# 04_LMS7002M_Misc.net
KiCad netlist of a schematic drawn in Altium Designer
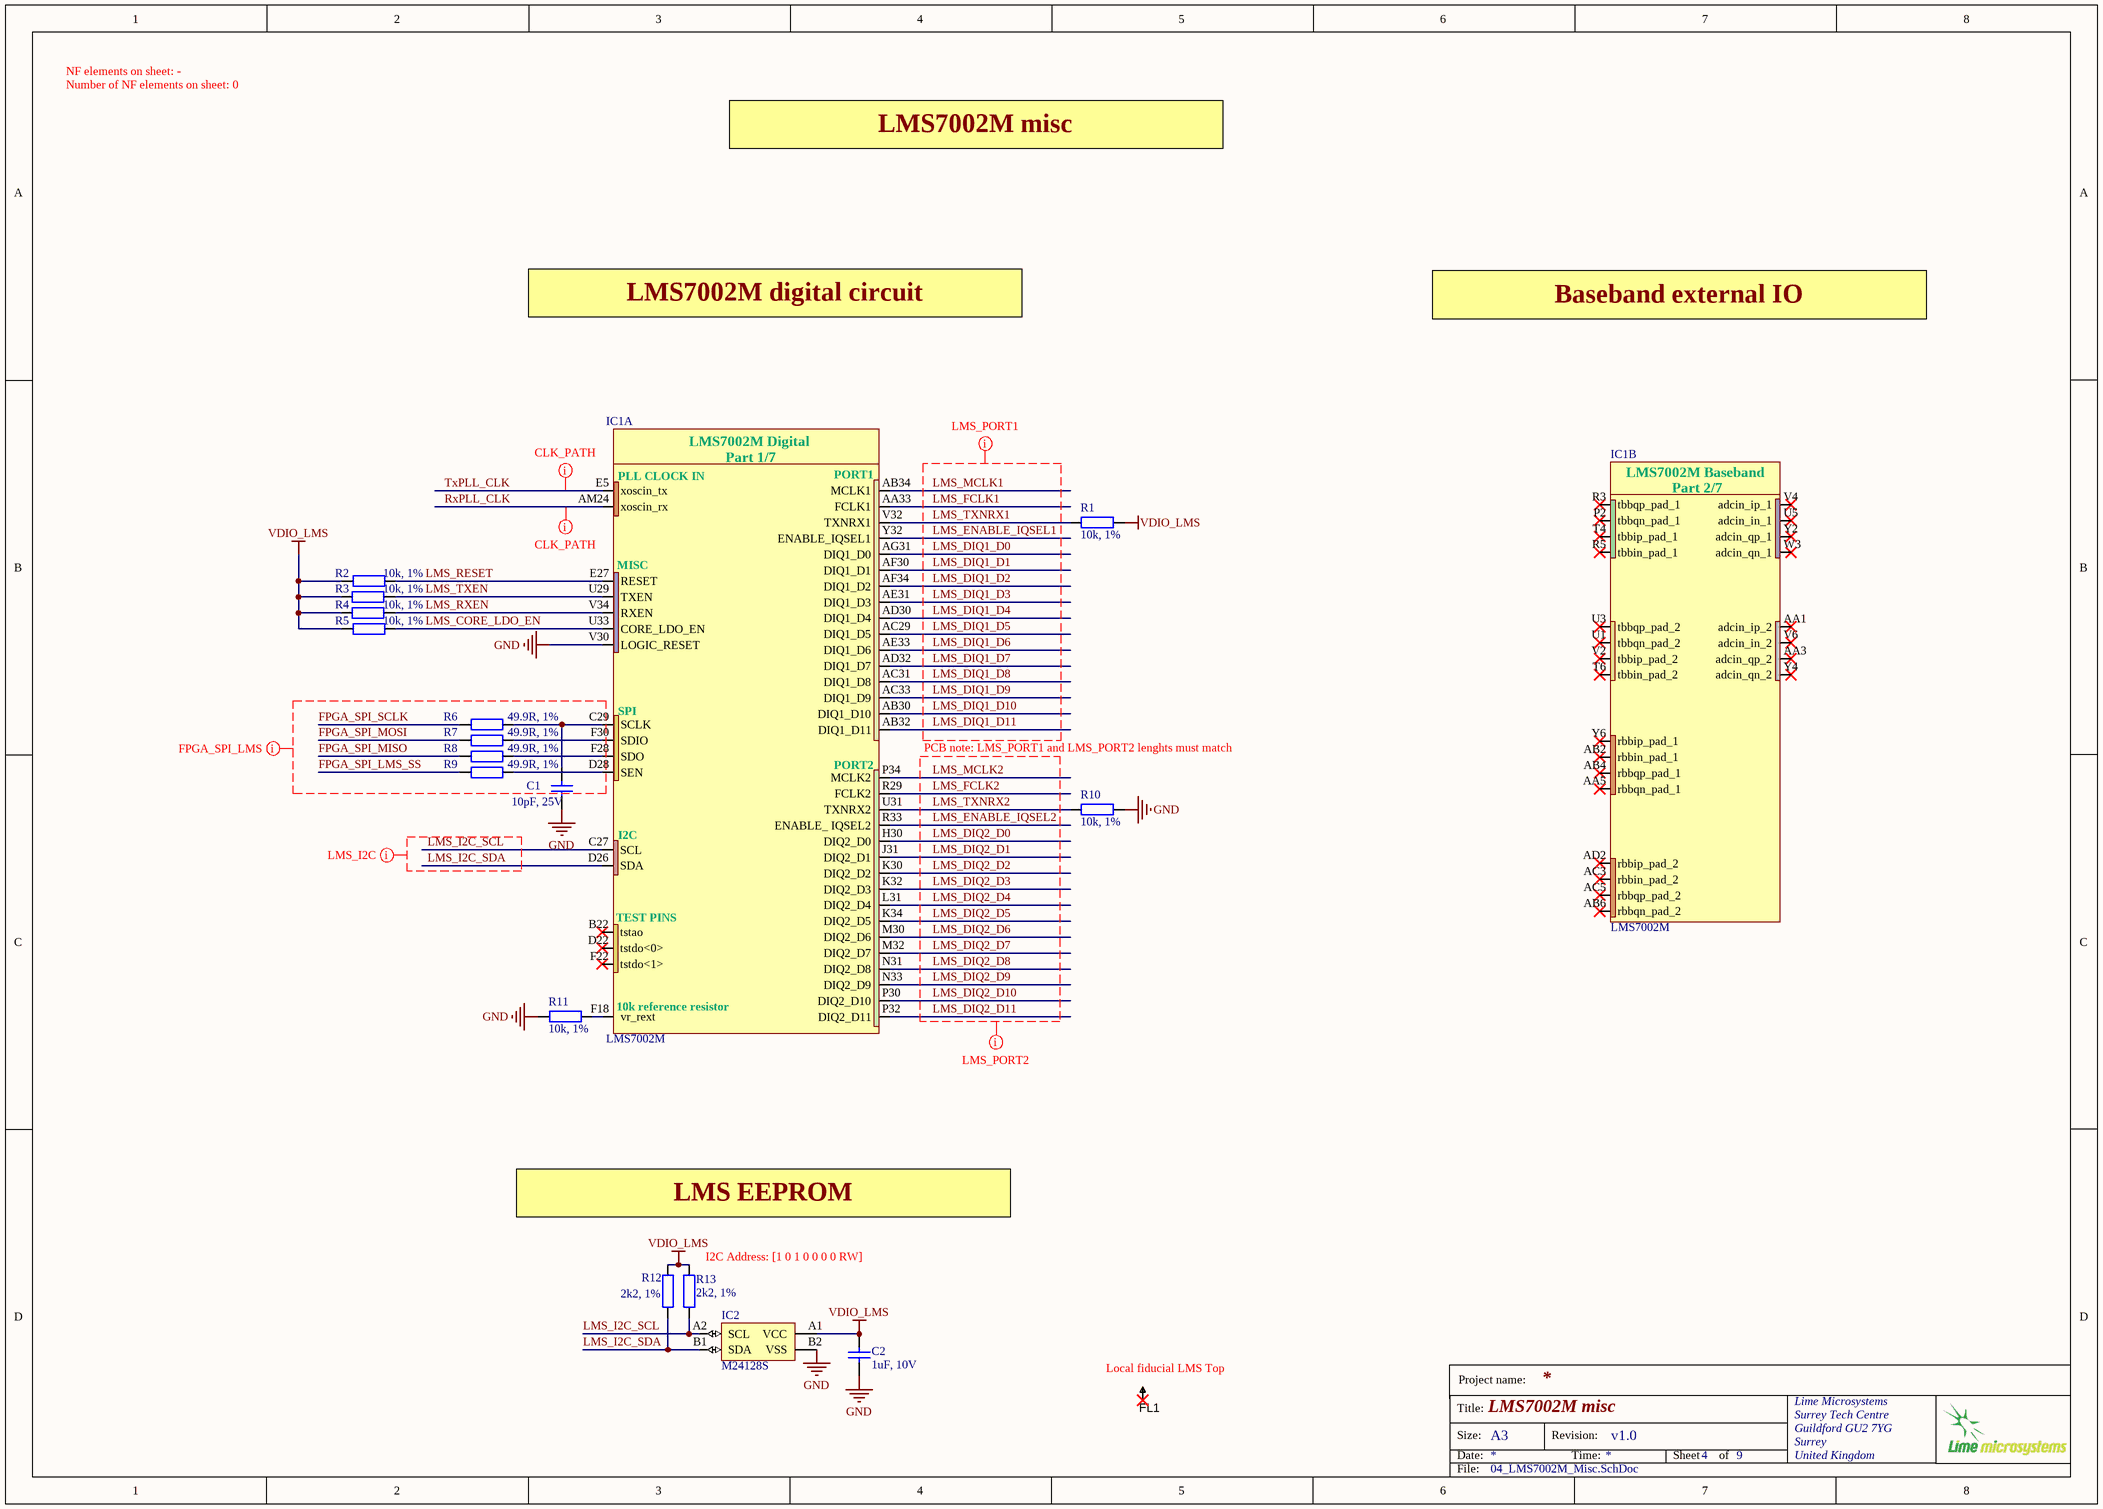
[diagram p0: 04_LMS7002M_Misc.SchDoc]

(export (version "E")
  (design (tool "Eeschema 10.0.6"))
  (components
    (comp (ref "C1")
      (value "10pF, 25V")
      (footprint "CAP0402")
      (fields (field (name "MANUFACTURER") "AVX"))
      (libsource (lib "LimeMicroAltiumLib_schLib") (part "Cap_0402"))
    )
    (comp (ref "C2")
      (value "1uF, 10V")
      (footprint "CAP0402")
      (fields (field (name "MANUFACTURER") "TDK"))
      (libsource (lib "LimeMicroAltiumLib_schLib") (part "Cap_0402"))
    )
    (comp (ref "FL1")
      (value "Fiducial")
      (footprint "Fiducial_local")
      (libsource (lib "VGTU_Altium_lib") (part "Fiducial"))
    )
    (comp (ref "IC1")
      (value "LMS7002M")
      (footprint "LMS7002M_v4")
      (description "Schematic symbol revision 3. Default footprint - 0.31mm pad")
      (fields (field (name "MANUFACTURER") "Lime Microsystems"))
      (libsource (lib "LimeMicroAltiumLib_schLib") (part "LMS7002Mr3"))
    )
    (comp (ref "IC2")
      (value "M24128S")
      (footprint "M24128S")
      (fields (field (name "MANUFACTURER") "STMicroelectronics"))
      (libsource (lib "LimeMicroAltiumLib_schLib") (part "M24128S"))
    )
    (comp (ref "R1")
      (value "10k, 1%")
      (footprint "RES0402")
      (fields (field (name "MANUFACTURER") "Yageo") (field (name "TOLERANCE") "±1%"))
      (libsource (lib "LimeMicroAltiumLib_schLib") (part "Res_0402"))
    )
    (comp (ref "R2")
      (value "10k, 1%")
      (footprint "RES0402")
      (fields (field (name "MANUFACTURER") "Yageo") (field (name "TOLERANCE") "±1%"))
      (libsource (lib "LimeMicroAltiumLib_schLib") (part "Res_0402"))
    )
    (comp (ref "R3")
      (value "10k, 1%")
      (footprint "RES0402")
      (fields (field (name "MANUFACTURER") "Yageo") (field (name "TOLERANCE") "±1%"))
      (libsource (lib "LimeMicroAltiumLib_schLib") (part "Res_0402"))
    )
    (comp (ref "R4")
      (value "10k, 1%")
      (footprint "RES0402")
      (fields (field (name "MANUFACTURER") "Yageo") (field (name "TOLERANCE") "±1%"))
      (libsource (lib "LimeMicroAltiumLib_schLib") (part "Res_0402"))
    )
    (comp (ref "R5")
      (value "10k, 1%")
      (footprint "RES0402")
      (fields (field (name "MANUFACTURER") "Yageo") (field (name "TOLERANCE") "±1%"))
      (libsource (lib "LimeMicroAltiumLib_schLib") (part "Res_0402"))
    )
    (comp (ref "R6")
      (value "49.9R, 1%")
      (footprint "RES0402")
      (fields
        (field (name "TOLERANCE") "±1%")
        (field (name "MANUFACTURER") "Samsung Electro-Mechanics America, Inc.")
        (field (name "MANUFACTURER PART NUMBER") "RC1005F49R9CS")
      )
      (libsource (lib "LimeMicroAltiumLib_schLib") (part "Res_0402"))
    )
    (comp (ref "R7")
      (value "49.9R, 1%")
      (footprint "RES0402")
      (fields
        (field (name "TOLERANCE") "±1%")
        (field (name "MANUFACTURER") "Samsung Electro-Mechanics America, Inc.")
        (field (name "MANUFACTURER PART NUMBER") "RC1005F49R9CS")
      )
      (libsource (lib "LimeMicroAltiumLib_schLib") (part "Res_0402"))
    )
    (comp (ref "R8")
      (value "49.9R, 1%")
      (footprint "RES0402")
      (fields
        (field (name "TOLERANCE") "±1%")
        (field (name "MANUFACTURER") "Samsung Electro-Mechanics America, Inc.")
        (field (name "MANUFACTURER PART NUMBER") "RC1005F49R9CS")
      )
      (libsource (lib "LimeMicroAltiumLib_schLib") (part "Res_0402"))
    )
    (comp (ref "R9")
      (value "49.9R, 1%")
      (footprint "RES0402")
      (fields
        (field (name "TOLERANCE") "±1%")
        (field (name "MANUFACTURER") "Samsung Electro-Mechanics America, Inc.")
        (field (name "MANUFACTURER PART NUMBER") "RC1005F49R9CS")
      )
      (libsource (lib "LimeMicroAltiumLib_schLib") (part "Res_0402"))
    )
    (comp (ref "R10")
      (value "10k, 1%")
      (footprint "RES0402")
      (fields (field (name "MANUFACTURER") "Yageo") (field (name "TOLERANCE") "±1%"))
      (libsource (lib "LimeMicroAltiumLib_schLib") (part "Res_0402"))
    )
    (comp (ref "R11")
      (value "10k, 1%")
      (footprint "RES0402")
      (fields (field (name "MANUFACTURER") "Yageo") (field (name "TOLERANCE") "±1%"))
      (libsource (lib "LimeMicroAltiumLib_schLib") (part "Res_0402"))
    )
    (comp (ref "R12")
      (value "2k2, 1%")
      (footprint "RES0402")
      (fields (field (name "MANUFACTURER") "Stackpole Electronics Inc") (field (name "TOLERANCE") "±1%"))
      (libsource (lib "LimeMicroAltiumLib_schLib") (part "Res_0402"))
    )
    (comp (ref "R13")
      (value "2k2, 1%")
      (footprint "RES0402")
      (fields (field (name "MANUFACTURER") "Stackpole Electronics Inc") (field (name "TOLERANCE") "±1%"))
      (libsource (lib "LimeMicroAltiumLib_schLib") (part "Res_0402"))
    )
  )
  (nets
    (net (code "1") (name "/FPGA_SPI_LMS_SS") (class "Default")
      (node (ref "R9") (pin "2") (pinfunction "2_2") (pintype "passive"))
    )
    (net (code "2") (name "/FPGA_SPI_MISO") (class "Default")
      (node (ref "R8") (pin "2") (pinfunction "2_2") (pintype "passive"))
    )
    (net (code "3") (name "/FPGA_SPI_MOSI") (class "Default")
      (node (ref "R7") (pin "2") (pinfunction "2_2") (pintype "passive"))
    )
    (net (code "4") (name "/FPGA_SPI_SCLK") (class "Default")
      (node (ref "R6") (pin "2") (pinfunction "2_2") (pintype "passive"))
    )
    (net (code "5") (name "/LMS_CORE_LDO_EN") (class "Default")
      (node (ref "IC1") (pin "U33") (pinfunction "CORE_LDO_EN_U33") (pintype "passive"))
      (node (ref "R5") (pin "1") (pinfunction "1_1") (pintype "passive"))
    )
    (net (code "6") (name "/LMS_DIQ1_D0") (class "Default")
      (node (ref "IC1") (pin "AG31") (pinfunction "DIQ1_D0_AG31") (pintype "passive"))
    )
    (net (code "7") (name "/LMS_DIQ1_D1") (class "Default")
      (node (ref "IC1") (pin "AF30") (pinfunction "DIQ1_D1_AF30") (pintype "passive"))
    )
    (net (code "8") (name "/LMS_DIQ1_D2") (class "Default")
      (node (ref "IC1") (pin "AF34") (pinfunction "DIQ1_D2_AF34") (pintype "passive"))
    )
    (net (code "9") (name "/LMS_DIQ1_D3") (class "Default")
      (node (ref "IC1") (pin "AE31") (pinfunction "DIQ1_D3_AE31") (pintype "passive"))
    )
    (net (code "10") (name "/LMS_DIQ1_D4") (class "Default")
      (node (ref "IC1") (pin "AD30") (pinfunction "DIQ1_D4_AD30") (pintype "passive"))
    )
    (net (code "11") (name "/LMS_DIQ1_D5") (class "Default")
      (node (ref "IC1") (pin "AC29") (pinfunction "DIQ1_D5_AC29") (pintype "passive"))
    )
    (net (code "12") (name "/LMS_DIQ1_D6") (class "Default")
      (node (ref "IC1") (pin "AE33") (pinfunction "DIQ1_D6_AE33") (pintype "passive"))
    )
    (net (code "13") (name "/LMS_DIQ1_D7") (class "Default")
      (node (ref "IC1") (pin "AD32") (pinfunction "DIQ1_D7_AD32") (pintype "passive"))
    )
    (net (code "14") (name "/LMS_DIQ1_D8") (class "Default")
      (node (ref "IC1") (pin "AC31") (pinfunction "DIQ1_D8_AC31") (pintype "passive"))
    )
    (net (code "15") (name "/LMS_DIQ1_D9") (class "Default")
      (node (ref "IC1") (pin "AC33") (pinfunction "DIQ1_D9_AC33") (pintype "passive"))
    )
    (net (code "16") (name "/LMS_DIQ1_D10") (class "Default")
      (node (ref "IC1") (pin "AB30") (pinfunction "DIQ1_D10_AB30") (pintype "passive"))
    )
    (net (code "17") (name "/LMS_DIQ1_D11") (class "Default")
      (node (ref "IC1") (pin "AB32") (pinfunction "DIQ1_D11_AB32") (pintype "passive"))
    )
    (net (code "18") (name "/LMS_DIQ2_D0") (class "Default")
      (node (ref "IC1") (pin "H30") (pinfunction "DIQ2_D0_H30") (pintype "passive"))
    )
    (net (code "19") (name "/LMS_DIQ2_D1") (class "Default")
      (node (ref "IC1") (pin "J31") (pinfunction "DIQ2_D1_J31") (pintype "passive"))
    )
    (net (code "20") (name "/LMS_DIQ2_D2") (class "Default")
      (node (ref "IC1") (pin "K30") (pinfunction "DIQ2_D2_K30") (pintype "passive"))
    )
    (net (code "21") (name "/LMS_DIQ2_D3") (class "Default")
      (node (ref "IC1") (pin "K32") (pinfunction "DIQ2_D3_K32") (pintype "passive"))
    )
    (net (code "22") (name "/LMS_DIQ2_D4") (class "Default")
      (node (ref "IC1") (pin "L31") (pinfunction "DIQ2_D4_L31") (pintype "passive"))
    )
    (net (code "23") (name "/LMS_DIQ2_D5") (class "Default")
      (node (ref "IC1") (pin "K34") (pinfunction "DIQ2_D5_K34") (pintype "passive"))
    )
    (net (code "24") (name "/LMS_DIQ2_D6") (class "Default")
      (node (ref "IC1") (pin "M30") (pinfunction "DIQ2_D6_M30") (pintype "passive"))
    )
    (net (code "25") (name "/LMS_DIQ2_D7") (class "Default")
      (node (ref "IC1") (pin "M32") (pinfunction "DIQ2_D7_M32") (pintype "passive"))
    )
    (net (code "26") (name "/LMS_DIQ2_D8") (class "Default")
      (node (ref "IC1") (pin "N31") (pinfunction "DIQ2_D8_N31") (pintype "passive"))
    )
    (net (code "27") (name "/LMS_DIQ2_D9") (class "Default")
      (node (ref "IC1") (pin "N33") (pinfunction "DIQ2_D9_N33") (pintype "passive"))
    )
    (net (code "28") (name "/LMS_DIQ2_D10") (class "Default")
      (node (ref "IC1") (pin "P30") (pinfunction "DIQ2_D10_P30") (pintype "passive"))
    )
    (net (code "29") (name "/LMS_DIQ2_D11") (class "Default")
      (node (ref "IC1") (pin "P32") (pinfunction "DIQ2_D11_P32") (pintype "passive"))
    )
    (net (code "30") (name "/LMS_ENABLE_IQSEL1") (class "Default")
      (node (ref "IC1") (pin "Y32") (pinfunction "ENABLE_IQSEL1_Y32") (pintype "passive"))
    )
    (net (code "31") (name "/LMS_ENABLE_IQSEL2") (class "Default")
      (node (ref "IC1") (pin "R33") (pinfunction "ENABLE__IQSEL2_R33") (pintype "passive"))
    )
    (net (code "32") (name "/LMS_FCLK1") (class "Default")
      (node (ref "IC1") (pin "AA33") (pinfunction "FCLK1_AA33") (pintype "passive"))
    )
    (net (code "33") (name "/LMS_FCLK2") (class "Default")
      (node (ref "IC1") (pin "R29") (pinfunction "FCLK2_R29") (pintype "passive"))
    )
    (net (code "34") (name "/LMS_I2C_SCL") (class "Default")
      (node (ref "IC1") (pin "C27") (pinfunction "SCL_C27") (pintype "passive"))
      (node (ref "IC2") (pin "A2") (pinfunction "SCL_A2") (pintype "bidirectional"))
      (node (ref "R13") (pin "2") (pinfunction "2_2") (pintype "passive"))
    )
    (net (code "35") (name "/LMS_I2C_SDA") (class "Default")
      (node (ref "IC1") (pin "D26") (pinfunction "SDA_D26") (pintype "passive"))
      (node (ref "IC2") (pin "B1") (pinfunction "SDA_B1") (pintype "bidirectional"))
      (node (ref "R12") (pin "2") (pinfunction "2_2") (pintype "passive"))
    )
    (net (code "36") (name "/LMS_MCLK1") (class "Default")
      (node (ref "IC1") (pin "AB34") (pinfunction "MCLK1_AB34") (pintype "passive"))
    )
    (net (code "37") (name "/LMS_MCLK2") (class "Default")
      (node (ref "IC1") (pin "P34") (pinfunction "MCLK2_P34") (pintype "passive"))
    )
    (net (code "38") (name "/LMS_RESET") (class "Default")
      (node (ref "IC1") (pin "E27") (pinfunction "RESET_E27") (pintype "passive"))
      (node (ref "R2") (pin "1") (pinfunction "1_1") (pintype "passive"))
    )
    (net (code "39") (name "/LMS_RXEN") (class "Default")
      (node (ref "IC1") (pin "V34") (pinfunction "RXEN_V34") (pintype "passive"))
      (node (ref "R4") (pin "2") (pinfunction "2_2") (pintype "passive"))
    )
    (net (code "40") (name "/LMS_TXEN") (class "Default")
      (node (ref "IC1") (pin "U29") (pinfunction "TXEN_U29") (pintype "passive"))
      (node (ref "R3") (pin "2") (pinfunction "2_2") (pintype "passive"))
    )
    (net (code "41") (name "/LMS_TXNRX1") (class "Default")
      (node (ref "IC1") (pin "V32") (pinfunction "TXNRX1_V32") (pintype "passive"))
      (node (ref "R1") (pin "1") (pinfunction "1_1") (pintype "passive"))
    )
    (net (code "42") (name "/LMS_TXNRX2") (class "Default")
      (node (ref "IC1") (pin "U31") (pinfunction "TXNRX2_U31") (pintype "passive"))
      (node (ref "R10") (pin "1") (pinfunction "1_1") (pintype "passive"))
    )
    (net (code "43") (name "/RxPLL_CLK") (class "Default")
      (node (ref "IC1") (pin "AM24") (pinfunction "xoscin_rx_AM24") (pintype "passive"))
    )
    (net (code "44") (name "/TxPLL_CLK") (class "Default")
      (node (ref "IC1") (pin "E5") (pinfunction "xoscin_tx_E5") (pintype "passive"))
    )
    (net (code "45") (name "GND") (class "Default")
      (node (ref "C1") (pin "2") (pinfunction "2_2") (pintype "passive"))
      (node (ref "C2") (pin "2") (pinfunction "2_2") (pintype "passive"))
      (node (ref "IC1") (pin "V30") (pinfunction "LOGIC_RESET_V30") (pintype "passive"))
      (node (ref "IC2") (pin "B2") (pinfunction "VSS_B2") (pintype "passive"))
      (node (ref "R10") (pin "2") (pinfunction "2_2") (pintype "passive"))
      (node (ref "R11") (pin "2") (pinfunction "2_2") (pintype "passive"))
    )
    (net (code "46") (name "Net-(IC1A-SCLK)") (class "Default")
      (node (ref "C1") (pin "1") (pinfunction "1_1") (pintype "passive"))
      (node (ref "IC1") (pin "C29") (pinfunction "SCLK_C29") (pintype "passive"))
      (node (ref "R6") (pin "1") (pinfunction "1_1") (pintype "passive"))
    )
    (net (code "47") (name "Net-(IC1A-SDIO)") (class "Default")
      (node (ref "IC1") (pin "F30") (pinfunction "SDIO_F30") (pintype "passive"))
      (node (ref "R7") (pin "1") (pinfunction "1_1") (pintype "passive"))
    )
    (net (code "48") (name "Net-(IC1A-SDO)") (class "Default")
      (node (ref "IC1") (pin "F28") (pinfunction "SDO_F28") (pintype "passive"))
      (node (ref "R8") (pin "1") (pinfunction "1_1") (pintype "passive"))
    )
    (net (code "49") (name "Net-(IC1A-SEN)") (class "Default")
      (node (ref "IC1") (pin "D28") (pinfunction "SEN_D28") (pintype "passive"))
      (node (ref "R9") (pin "1") (pinfunction "1_1") (pintype "passive"))
    )
    (net (code "50") (name "Net-(IC1A-vr_rext)") (class "Default")
      (node (ref "IC1") (pin "F18") (pinfunction "vr_rext_F18") (pintype "passive"))
      (node (ref "R11") (pin "1") (pinfunction "1_1") (pintype "passive"))
    )
    (net (code "51") (name "VDIO_LMS") (class "Default")
      (node (ref "C2") (pin "1") (pinfunction "1_1") (pintype "passive"))
      (node (ref "IC2") (pin "A1") (pinfunction "VCC_A1") (pintype "passive"))
      (node (ref "R1") (pin "2") (pinfunction "2_2") (pintype "passive"))
      (node (ref "R12") (pin "1") (pinfunction "1_1") (pintype "passive"))
      (node (ref "R13") (pin "1") (pinfunction "1_1") (pintype "passive"))
      (node (ref "R2") (pin "2") (pinfunction "2_2") (pintype "passive"))
      (node (ref "R3") (pin "1") (pinfunction "1_1") (pintype "passive"))
      (node (ref "R4") (pin "1") (pinfunction "1_1") (pintype "passive"))
      (node (ref "R5") (pin "2") (pinfunction "2_2") (pintype "passive"))
    )
    (net (code "52") (name "unconnected-(FL1-Pad1)") (class "Default")
      (node (ref "FL1") (pin "1") (pintype "passive+no_connect"))
    )
    (net (code "53") (name "unconnected-(IC1A-tstao-PadB22)") (class "Default")
      (node (ref "IC1") (pin "B22") (pinfunction "tstao_B22") (pintype "passive+no_connect"))
    )
    (net (code "54") (name "unconnected-(IC1A-tstdo<0>-PadD22)") (class "Default")
      (node (ref "IC1") (pin "D22") (pinfunction "tstdo<0>_D22") (pintype "passive+no_connect"))
    )
    (net (code "55") (name "unconnected-(IC1A-tstdo<1>-PadF22)") (class "Default")
      (node (ref "IC1") (pin "F22") (pinfunction "tstdo<1>_F22") (pintype "passive+no_connect"))
    )
    (net (code "56") (name "unconnected-(IC1B-adcin_in_1-PadU5)") (class "Default")
      (node (ref "IC1") (pin "U5") (pinfunction "adcin_in_1_U5") (pintype "passive+no_connect"))
    )
    (net (code "57") (name "unconnected-(IC1B-adcin_in_2-PadV6)") (class "Default")
      (node (ref "IC1") (pin "V6") (pinfunction "adcin_in_2_V6") (pintype "passive+no_connect"))
    )
    (net (code "58") (name "unconnected-(IC1B-adcin_ip_1-PadV4)") (class "Default")
      (node (ref "IC1") (pin "V4") (pinfunction "adcin_ip_1_V4") (pintype "passive+no_connect"))
    )
    (net (code "59") (name "unconnected-(IC1B-adcin_ip_2-PadAA1)") (class "Default")
      (node (ref "IC1") (pin "AA1") (pinfunction "adcin_ip_2_AA1") (pintype "passive+no_connect"))
    )
    (net (code "60") (name "unconnected-(IC1B-adcin_qn_1-PadW3)") (class "Default")
      (node (ref "IC1") (pin "W3") (pinfunction "adcin_qn_1_W3") (pintype "passive+no_connect"))
    )
    (net (code "61") (name "unconnected-(IC1B-adcin_qn_2-PadY4)") (class "Default")
      (node (ref "IC1") (pin "Y4") (pinfunction "adcin_qn_2_Y4") (pintype "passive+no_connect"))
    )
    (net (code "62") (name "unconnected-(IC1B-adcin_qp_1-PadY2)") (class "Default")
      (node (ref "IC1") (pin "Y2") (pinfunction "adcin_qp_1_Y2") (pintype "passive+no_connect"))
    )
    (net (code "63") (name "unconnected-(IC1B-adcin_qp_2-PadAA3)") (class "Default")
      (node (ref "IC1") (pin "AA3") (pinfunction "adcin_qp_2_AA3") (pintype "passive+no_connect"))
    )
    (net (code "64") (name "unconnected-(IC1B-rbbin_pad_1-PadAB2)") (class "Default")
      (node (ref "IC1") (pin "AB2") (pinfunction "rbbin_pad_1_AB2") (pintype "passive+no_connect"))
    )
    (net (code "65") (name "unconnected-(IC1B-rbbin_pad_2-PadAC3)") (class "Default")
      (node (ref "IC1") (pin "AC3") (pinfunction "rbbin_pad_2_AC3") (pintype "passive+no_connect"))
    )
    (net (code "66") (name "unconnected-(IC1B-rbbip_pad_1-PadY6)") (class "Default")
      (node (ref "IC1") (pin "Y6") (pinfunction "rbbip_pad_1_Y6") (pintype "passive+no_connect"))
    )
    (net (code "67") (name "unconnected-(IC1B-rbbip_pad_2-PadAD2)") (class "Default")
      (node (ref "IC1") (pin "AD2") (pinfunction "rbbip_pad_2_AD2") (pintype "passive+no_connect"))
    )
    (net (code "68") (name "unconnected-(IC1B-rbbqn_pad_1-PadAA5)") (class "Default")
      (node (ref "IC1") (pin "AA5") (pinfunction "rbbqn_pad_1_AA5") (pintype "passive+no_connect"))
    )
    (net (code "69") (name "unconnected-(IC1B-rbbqn_pad_2-PadAB6)") (class "Default")
      (node (ref "IC1") (pin "AB6") (pinfunction "rbbqn_pad_2_AB6") (pintype "passive+no_connect"))
    )
    (net (code "70") (name "unconnected-(IC1B-rbbqp_pad_1-PadAB4)") (class "Default")
      (node (ref "IC1") (pin "AB4") (pinfunction "rbbqp_pad_1_AB4") (pintype "passive+no_connect"))
    )
    (net (code "71") (name "unconnected-(IC1B-rbbqp_pad_2-PadAC5)") (class "Default")
      (node (ref "IC1") (pin "AC5") (pinfunction "rbbqp_pad_2_AC5") (pintype "passive+no_connect"))
    )
    (net (code "72") (name "unconnected-(IC1B-tbbin_pad_1-PadR5)") (class "Default")
      (node (ref "IC1") (pin "R5") (pinfunction "tbbin_pad_1_R5") (pintype "passive+no_connect"))
    )
    (net (code "73") (name "unconnected-(IC1B-tbbin_pad_2-PadT6)") (class "Default")
      (node (ref "IC1") (pin "T6") (pinfunction "tbbin_pad_2_T6") (pintype "passive+no_connect"))
    )
    (net (code "74") (name "unconnected-(IC1B-tbbip_pad_1-PadT4)") (class "Default")
      (node (ref "IC1") (pin "T4") (pinfunction "tbbip_pad_1_T4") (pintype "passive+no_connect"))
    )
    (net (code "75") (name "unconnected-(IC1B-tbbip_pad_2-PadV2)") (class "Default")
      (node (ref "IC1") (pin "V2") (pinfunction "tbbip_pad_2_V2") (pintype "passive+no_connect"))
    )
    (net (code "76") (name "unconnected-(IC1B-tbbqn_pad_1-PadP2)") (class "Default")
      (node (ref "IC1") (pin "P2") (pinfunction "tbbqn_pad_1_P2") (pintype "passive+no_connect"))
    )
    (net (code "77") (name "unconnected-(IC1B-tbbqn_pad_2-PadU1)") (class "Default")
      (node (ref "IC1") (pin "U1") (pinfunction "tbbqn_pad_2_U1") (pintype "passive+no_connect"))
    )
    (net (code "78") (name "unconnected-(IC1B-tbbqp_pad_1-PadR3)") (class "Default")
      (node (ref "IC1") (pin "R3") (pinfunction "tbbqp_pad_1_R3") (pintype "passive+no_connect"))
    )
    (net (code "79") (name "unconnected-(IC1B-tbbqp_pad_2-PadU3)") (class "Default")
      (node (ref "IC1") (pin "U3") (pinfunction "tbbqp_pad_2_U3") (pintype "passive+no_connect"))
    )
  )
)
